# RedundantReg.net
KiCad netlist of a schematic drawn in Altium Designer
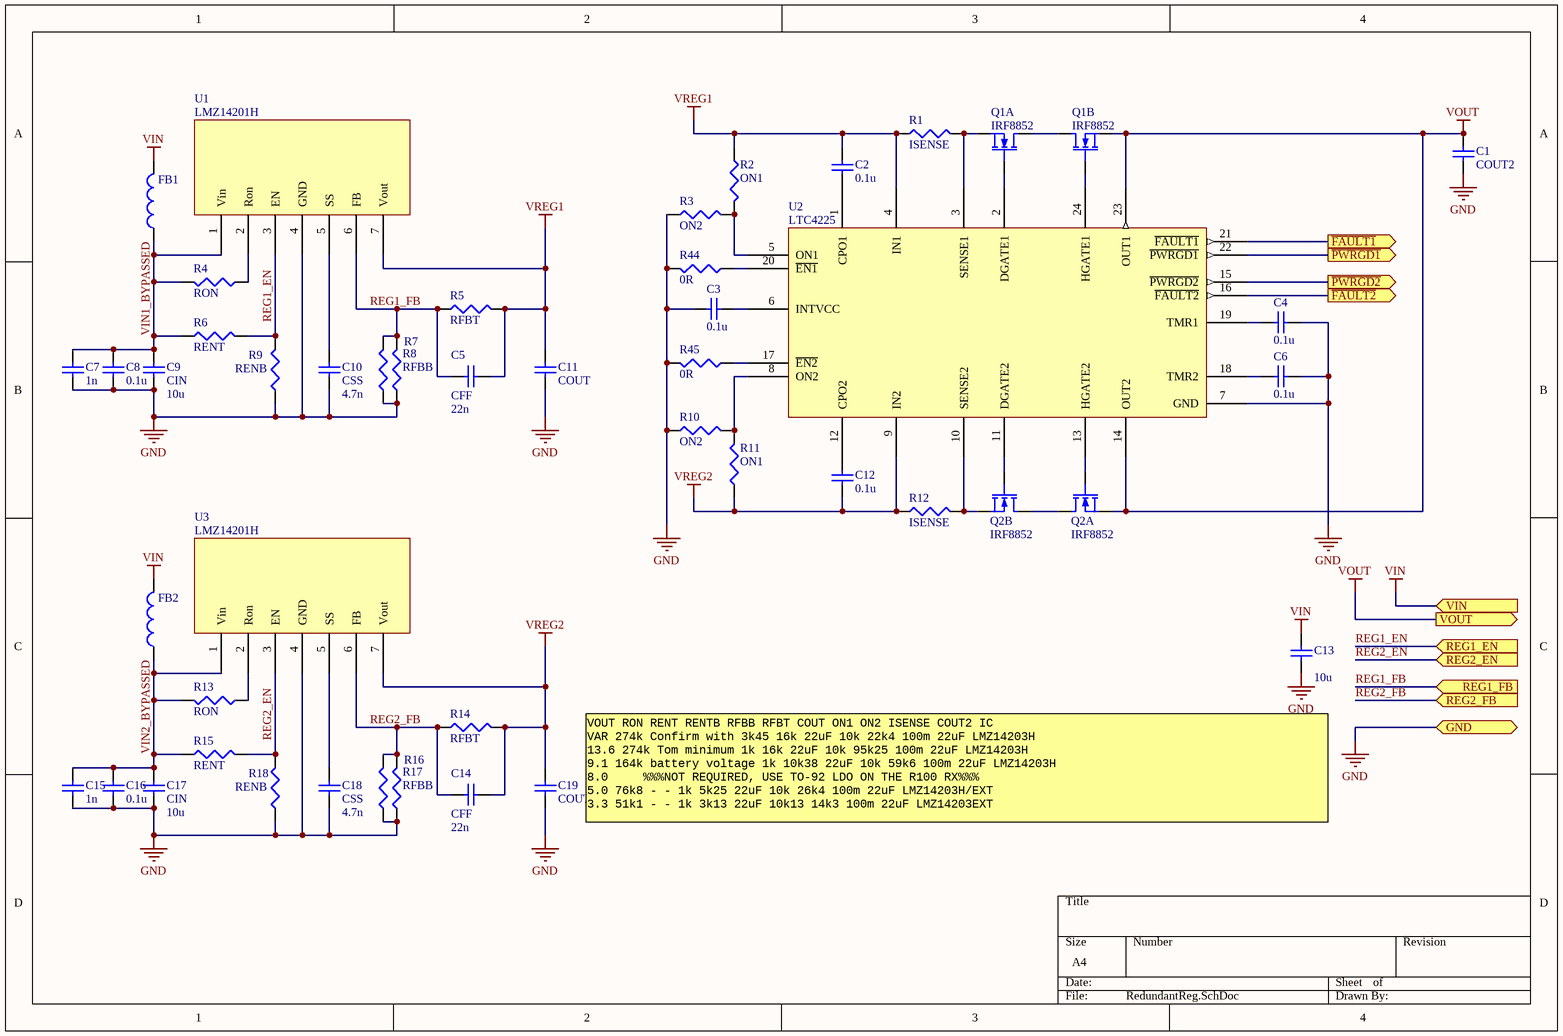
[diagram p0: RedundantReg.SchDoc]

(export (version "E")
  (design (tool "Eeschema 10.0.6"))
  (components
    (comp (ref "C1")
      (value "COUT2")
      (footprint "R1210M")
      (description "Capacitor")
      (fields (field (name "PUBLISHER") "Altium Limited"))
      (libsource (lib "Miscellaneous Devices") (part "Cap"))
    )
    (comp (ref "C2")
      (value "0.1u")
      (footprint "R0805M")
      (description "Capacitor")
      (fields (field (name "PUBLISHER") "Altium Limited"))
      (libsource (lib "Miscellaneous Devices") (part "Cap"))
    )
    (comp (ref "C3")
      (value "0.1u")
      (footprint "R0805M")
      (description "Capacitor")
      (fields (field (name "PUBLISHER") "Altium Limited"))
      (libsource (lib "Miscellaneous Devices") (part "Cap"))
    )
    (comp (ref "C4")
      (value "0.1u")
      (footprint "R0805M")
      (description "Capacitor")
      (fields (field (name "PUBLISHER") "Altium Limited"))
      (libsource (lib "Miscellaneous Devices") (part "Cap"))
    )
    (comp (ref "C5")
      (value "CFF")
      (footprint "R0805M")
      (description "Capacitor")
      (fields (field (name "ALTIUM_VALUE") "22n") (field (name "PUBLISHER") "Altium Limited"))
      (libsource (lib "Miscellaneous Devices") (part "Cap"))
    )
    (comp (ref "C6")
      (value "0.1u")
      (footprint "R0805M")
      (description "Capacitor")
      (fields (field (name "PUBLISHER") "Altium Limited"))
      (libsource (lib "Miscellaneous Devices") (part "Cap"))
    )
    (comp (ref "C7")
      (value "1n")
      (footprint "R0805M")
      (description "Capacitor")
      (fields (field (name "Comment") "CIN") (field (name "PUBLISHER") "Altium Limited"))
      (libsource (lib "Miscellaneous Devices") (part "Cap"))
    )
    (comp (ref "C8")
      (value "0.1u")
      (footprint "R0805M")
      (description "Capacitor")
      (fields (field (name "Comment") "CIN") (field (name "PUBLISHER") "Altium Limited"))
      (libsource (lib "Miscellaneous Devices") (part "Cap"))
    )
    (comp (ref "C9")
      (value "CIN")
      (footprint "R1210M")
      (description "Capacitor")
      (fields (field (name "ALTIUM_VALUE") "10u") (field (name "PUBLISHER") "Altium Limited"))
      (libsource (lib "Miscellaneous Devices") (part "Cap"))
    )
    (comp (ref "C10")
      (value "CSS")
      (footprint "R0805M")
      (description "Capacitor")
      (fields (field (name "ALTIUM_VALUE") "4.7n") (field (name "PUBLISHER") "Altium Limited"))
      (libsource (lib "Miscellaneous Devices") (part "Cap"))
    )
    (comp (ref "C11")
      (value "COUT")
      (footprint "R1210M")
      (description "Capacitor")
      (fields (field (name "PUBLISHER") "Altium Limited"))
      (libsource (lib "Miscellaneous Devices") (part "Cap"))
    )
    (comp (ref "C12")
      (value "0.1u")
      (footprint "R0805M")
      (description "Capacitor")
      (fields (field (name "PUBLISHER") "Altium Limited"))
      (libsource (lib "Miscellaneous Devices") (part "Cap"))
    )
    (comp (ref "C13")
      (value "10u")
      (footprint "R1210M")
      (description "Capacitor")
      (fields (field (name "PUBLISHER") "Altium Limited"))
      (libsource (lib "Miscellaneous Devices") (part "Cap"))
    )
    (comp (ref "C14")
      (value "CFF")
      (footprint "R0805M")
      (description "Capacitor")
      (fields (field (name "ALTIUM_VALUE") "22n") (field (name "PUBLISHER") "Altium Limited"))
      (libsource (lib "Miscellaneous Devices") (part "Cap"))
    )
    (comp (ref "C15")
      (value "1n")
      (footprint "R0805M")
      (description "Capacitor")
      (fields (field (name "Comment") "CIN") (field (name "PUBLISHER") "Altium Limited"))
      (libsource (lib "Miscellaneous Devices") (part "Cap"))
    )
    (comp (ref "C16")
      (value "0.1u")
      (footprint "R0805M")
      (description "Capacitor")
      (fields (field (name "Comment") "CIN") (field (name "PUBLISHER") "Altium Limited"))
      (libsource (lib "Miscellaneous Devices") (part "Cap"))
    )
    (comp (ref "C17")
      (value "CIN")
      (footprint "R1210M")
      (description "Capacitor")
      (fields (field (name "ALTIUM_VALUE") "10u") (field (name "PUBLISHER") "Altium Limited"))
      (libsource (lib "Miscellaneous Devices") (part "Cap"))
    )
    (comp (ref "C18")
      (value "CSS")
      (footprint "R0805M")
      (description "Capacitor")
      (fields (field (name "ALTIUM_VALUE") "4.7n") (field (name "PUBLISHER") "Altium Limited"))
      (libsource (lib "Miscellaneous Devices") (part "Cap"))
    )
    (comp (ref "C19")
      (value "COUT")
      (footprint "R1210M")
      (description "Capacitor")
      (fields (field (name "PUBLISHER") "Altium Limited"))
      (libsource (lib "Miscellaneous Devices") (part "Cap"))
    )
    (comp (ref "FB1")
      (value "~")
      (footprint "R0805M")
      (description "Inductor")
      (fields (field (name "PUBLISHER") "Altium Limited"))
      (libsource (lib "Miscellaneous Devices") (part "Inductor"))
    )
    (comp (ref "FB2")
      (value "~")
      (footprint "R0805M")
      (description "Inductor")
      (fields (field (name "PUBLISHER") "Altium Limited"))
      (libsource (lib "Miscellaneous Devices") (part "Inductor"))
    )
    (comp (ref "Q1")
      (value "IRF8852")
      (footprint "TSSOP8")
      (description "N-Channel MOSFET")
      (fields (field (name "PUBLISHER") "Altium Limited"))
      (libsource (lib "SchLib") (part "IRF8852"))
    )
    (comp (ref "Q2")
      (value "IRF8852")
      (footprint "TSSOP8")
      (description "N-Channel MOSFET")
      (fields (field (name "PUBLISHER") "Altium Limited"))
      (libsource (lib "SchLib") (part "IRF8852"))
    )
    (comp (ref "R1")
      (value "ISENSE")
      (footprint "R0805M")
      (description "Resistor")
      (fields (field (name "PUBLISHER") "Altium Limited"))
      (libsource (lib "Miscellaneous Devices") (part "Res3"))
    )
    (comp (ref "R2")
      (value "ON1")
      (footprint "R0805M")
      (description "Resistor")
      (fields (field (name "PUBLISHER") "Altium Limited"))
      (libsource (lib "Miscellaneous Devices") (part "Res3"))
    )
    (comp (ref "R3")
      (value "ON2")
      (footprint "R0805M")
      (description "Resistor")
      (fields (field (name "PUBLISHER") "Altium Limited"))
      (libsource (lib "Miscellaneous Devices") (part "Res3"))
    )
    (comp (ref "R4")
      (value "RON")
      (footprint "R0805M")
      (description "Resistor")
      (fields (field (name "PUBLISHER") "Altium Limited"))
      (libsource (lib "Miscellaneous Devices") (part "Res3"))
    )
    (comp (ref "R5")
      (value "RFBT")
      (footprint "R0805M")
      (description "Resistor")
      (fields (field (name "PUBLISHER") "Altium Limited"))
      (libsource (lib "Miscellaneous Devices") (part "Res3"))
    )
    (comp (ref "R6")
      (value "RENT")
      (footprint "R0805M")
      (description "Resistor")
      (fields (field (name "PUBLISHER") "Altium Limited"))
      (libsource (lib "Miscellaneous Devices") (part "Res3"))
    )
    (comp (ref "R7")
      (value "RFBB")
      (footprint "R0805M")
      (description "Resistor")
      (fields (field (name "PUBLISHER") "Altium Limited"))
      (libsource (lib "Miscellaneous Devices") (part "Res3"))
    )
    (comp (ref "R8")
      (value "RFBB")
      (footprint "R0805M")
      (description "Resistor")
      (fields (field (name "PUBLISHER") "Altium Limited"))
      (libsource (lib "Miscellaneous Devices") (part "Res3"))
    )
    (comp (ref "R9")
      (value "RENB")
      (footprint "R0805M")
      (description "Resistor")
      (fields (field (name "PUBLISHER") "Altium Limited"))
      (libsource (lib "Miscellaneous Devices") (part "Res3"))
    )
    (comp (ref "R10")
      (value "ON2")
      (footprint "R0805M")
      (description "Resistor")
      (fields (field (name "PUBLISHER") "Altium Limited"))
      (libsource (lib "Miscellaneous Devices") (part "Res3"))
    )
    (comp (ref "R11")
      (value "ON1")
      (footprint "R0805M")
      (description "Resistor")
      (fields (field (name "PUBLISHER") "Altium Limited"))
      (libsource (lib "Miscellaneous Devices") (part "Res3"))
    )
    (comp (ref "R12")
      (value "ISENSE")
      (footprint "R0805M")
      (description "Resistor")
      (fields (field (name "PUBLISHER") "Altium Limited"))
      (libsource (lib "Miscellaneous Devices") (part "Res3"))
    )
    (comp (ref "R13")
      (value "RON")
      (footprint "R0805M")
      (description "Resistor")
      (fields (field (name "PUBLISHER") "Altium Limited"))
      (libsource (lib "Miscellaneous Devices") (part "Res3"))
    )
    (comp (ref "R14")
      (value "RFBT")
      (footprint "R0805M")
      (description "Resistor")
      (fields (field (name "PUBLISHER") "Altium Limited"))
      (libsource (lib "Miscellaneous Devices") (part "Res3"))
    )
    (comp (ref "R15")
      (value "RENT")
      (footprint "R0805M")
      (description "Resistor")
      (fields (field (name "PUBLISHER") "Altium Limited"))
      (libsource (lib "Miscellaneous Devices") (part "Res3"))
    )
    (comp (ref "R16")
      (value "RFBB")
      (footprint "R0805M")
      (description "Resistor")
      (fields (field (name "PUBLISHER") "Altium Limited"))
      (libsource (lib "Miscellaneous Devices") (part "Res3"))
    )
    (comp (ref "R17")
      (value "RFBB")
      (footprint "R0805M")
      (description "Resistor")
      (fields (field (name "PUBLISHER") "Altium Limited"))
      (libsource (lib "Miscellaneous Devices") (part "Res3"))
    )
    (comp (ref "R18")
      (value "RENB")
      (footprint "R0805M")
      (description "Resistor")
      (fields (field (name "PUBLISHER") "Altium Limited"))
      (libsource (lib "Miscellaneous Devices") (part "Res3"))
    )
    (comp (ref "R44")
      (value "0R")
      (footprint "R0805M")
      (description "Resistor")
      (fields (field (name "PUBLISHER") "Altium Limited"))
      (libsource (lib "Miscellaneous Devices") (part "Res3"))
    )
    (comp (ref "R45")
      (value "0R")
      (footprint "R0805M")
      (description "Resistor")
      (fields (field (name "PUBLISHER") "Altium Limited"))
      (libsource (lib "Miscellaneous Devices") (part "Res3"))
    )
    (comp (ref "U1")
      (value "LMZ14201H")
      (footprint "TO-PMOD-7")
      (description "1A SIMPLE SWITCHER® Power Module for High Output  Voltage")
      (libsource (lib "SchLib") (part "LMZ14201H"))
    )
    (comp (ref "U2")
      (value "LTC4225")
      (footprint "SSOP24")
      (description "Dual Ideal Diode and  Hot Swap Controller")
      (libsource (lib "SchLib") (part "LTC4225"))
    )
    (comp (ref "U3")
      (value "LMZ14201H")
      (footprint "TO-PMOD-7")
      (description "1A SIMPLE SWITCHER® Power Module for High Output  Voltage")
      (libsource (lib "SchLib") (part "LMZ14201H"))
    )
  )
  (nets
    (net (code "1") (name "/REG1_EN") (class "Default")
      (node (ref "R6") (pin "2") (pinfunction "2_2") (pintype "passive"))
      (node (ref "R9") (pin "1") (pinfunction "1_1") (pintype "passive"))
      (node (ref "U1") (pin "3") (pinfunction "EN_3") (pintype "passive"))
    )
    (net (code "2") (name "/REG1_FB") (class "Default")
      (node (ref "C5") (pin "1") (pinfunction "1_1") (pintype "passive"))
      (node (ref "R5") (pin "1") (pinfunction "1_1") (pintype "passive"))
      (node (ref "R7") (pin "2") (pinfunction "2_2") (pintype "passive"))
      (node (ref "R8") (pin "2") (pinfunction "2_2") (pintype "passive"))
      (node (ref "U1") (pin "6") (pinfunction "FB_6") (pintype "passive"))
    )
    (net (code "3") (name "/REG2_EN") (class "Default")
      (node (ref "R15") (pin "2") (pinfunction "2_2") (pintype "passive"))
      (node (ref "R18") (pin "1") (pinfunction "1_1") (pintype "passive"))
      (node (ref "U3") (pin "3") (pinfunction "EN_3") (pintype "passive"))
    )
    (net (code "4") (name "/REG2_FB") (class "Default")
      (node (ref "C14") (pin "1") (pinfunction "1_1") (pintype "passive"))
      (node (ref "R14") (pin "1") (pinfunction "1_1") (pintype "passive"))
      (node (ref "R16") (pin "2") (pinfunction "2_2") (pintype "passive"))
      (node (ref "R17") (pin "2") (pinfunction "2_2") (pintype "passive"))
      (node (ref "U3") (pin "6") (pinfunction "FB_6") (pintype "passive"))
    )
    (net (code "5") (name "/VIN1_BYPASSED") (class "Default")
      (node (ref "C7") (pin "2") (pinfunction "2_2") (pintype "passive"))
      (node (ref "C8") (pin "2") (pinfunction "2_2") (pintype "passive"))
      (node (ref "C9") (pin "1") (pinfunction "1_1") (pintype "passive"))
      (node (ref "FB1") (pin "1") (pinfunction "1_1") (pintype "passive"))
      (node (ref "R4") (pin "2") (pinfunction "2_2") (pintype "passive"))
      (node (ref "R6") (pin "1") (pinfunction "1_1") (pintype "passive"))
      (node (ref "U1") (pin "1") (pinfunction "Vin_1") (pintype "passive"))
    )
    (net (code "6") (name "/VIN2_BYPASSED") (class "Default")
      (node (ref "C15") (pin "2") (pinfunction "2_2") (pintype "passive"))
      (node (ref "C16") (pin "2") (pinfunction "2_2") (pintype "passive"))
      (node (ref "C17") (pin "1") (pinfunction "1_1") (pintype "passive"))
      (node (ref "FB2") (pin "1") (pinfunction "1_1") (pintype "passive"))
      (node (ref "R13") (pin "2") (pinfunction "2_2") (pintype "passive"))
      (node (ref "R15") (pin "1") (pinfunction "1_1") (pintype "passive"))
      (node (ref "U3") (pin "1") (pinfunction "Vin_1") (pintype "passive"))
    )
    (net (code "7") (name "/~{FAULT1}") (class "Default")
      (node (ref "U2") (pin "21") (pinfunction "~{FAULT1}_21") (pintype "output"))
    )
    (net (code "8") (name "/~{FAULT2}") (class "Default")
      (node (ref "U2") (pin "16") (pinfunction "~{FAULT2}_16") (pintype "output"))
    )
    (net (code "9") (name "/~{PWRGD1}") (class "Default")
      (node (ref "U2") (pin "22") (pinfunction "~{PWRGD1}_22") (pintype "output"))
    )
    (net (code "10") (name "/~{PWRGD2}") (class "Default")
      (node (ref "U2") (pin "15") (pinfunction "~{PWRGD2}_15") (pintype "output"))
    )
    (net (code "11") (name "GND") (class "Default")
      (node (ref "C1") (pin "1") (pinfunction "1_1") (pintype "passive"))
      (node (ref "C10") (pin "2") (pinfunction "2_2") (pintype "passive"))
      (node (ref "C11") (pin "1") (pinfunction "1_1") (pintype "passive"))
      (node (ref "C13") (pin "2") (pinfunction "2_2") (pintype "passive"))
      (node (ref "C15") (pin "1") (pinfunction "1_1") (pintype "passive"))
      (node (ref "C16") (pin "1") (pinfunction "1_1") (pintype "passive"))
      (node (ref "C17") (pin "2") (pinfunction "2_2") (pintype "passive"))
      (node (ref "C18") (pin "2") (pinfunction "2_2") (pintype "passive"))
      (node (ref "C19") (pin "1") (pinfunction "1_1") (pintype "passive"))
      (node (ref "C3") (pin "2") (pinfunction "2_2") (pintype "passive"))
      (node (ref "C4") (pin "1") (pinfunction "1_1") (pintype "passive"))
      (node (ref "C6") (pin "1") (pinfunction "1_1") (pintype "passive"))
      (node (ref "C7") (pin "1") (pinfunction "1_1") (pintype "passive"))
      (node (ref "C8") (pin "1") (pinfunction "1_1") (pintype "passive"))
      (node (ref "C9") (pin "2") (pinfunction "2_2") (pintype "passive"))
      (node (ref "R10") (pin "1") (pinfunction "1_1") (pintype "passive"))
      (node (ref "R16") (pin "1") (pinfunction "1_1") (pintype "passive"))
      (node (ref "R17") (pin "1") (pinfunction "1_1") (pintype "passive"))
      (node (ref "R18") (pin "2") (pinfunction "2_2") (pintype "passive"))
      (node (ref "R3") (pin "1") (pinfunction "1_1") (pintype "passive"))
      (node (ref "R44") (pin "2") (pinfunction "2_2") (pintype "passive"))
      (node (ref "R45") (pin "2") (pinfunction "2_2") (pintype "passive"))
      (node (ref "R7") (pin "1") (pinfunction "1_1") (pintype "passive"))
      (node (ref "R8") (pin "1") (pinfunction "1_1") (pintype "passive"))
      (node (ref "R9") (pin "2") (pinfunction "2_2") (pintype "passive"))
      (node (ref "U1") (pin "4") (pinfunction "GND_4") (pintype "passive"))
      (node (ref "U2") (pin "7") (pinfunction "GND_7") (pintype "passive"))
      (node (ref "U3") (pin "4") (pinfunction "GND_4") (pintype "passive"))
    )
    (net (code "12") (name "Net-(Q1A-D)") (class "Default")
      (node (ref "Q1") (pin "D1") (pinfunction "D_D1") (pintype "passive"))
      (node (ref "Q1") (pin "D2") (pinfunction "D_D2") (pintype "passive"))
    )
    (net (code "13") (name "Net-(Q1A-G)") (class "Default")
      (node (ref "Q1") (pin "G1") (pinfunction "G_G1") (pintype "passive"))
      (node (ref "U2") (pin "2") (pinfunction "DGATE1_2") (pintype "passive"))
    )
    (net (code "14") (name "Net-(Q1A-S)") (class "Default")
      (node (ref "Q1") (pin "S1") (pinfunction "S_S1") (pintype "passive"))
      (node (ref "R1") (pin "2") (pinfunction "2_2") (pintype "passive"))
      (node (ref "U2") (pin "3") (pinfunction "SENSE1_3") (pintype "passive"))
    )
    (net (code "15") (name "Net-(Q1B-G)") (class "Default")
      (node (ref "Q1") (pin "G2") (pinfunction "G_G2") (pintype "passive"))
      (node (ref "U2") (pin "24") (pinfunction "HGATE1_24") (pintype "passive"))
    )
    (net (code "16") (name "Net-(Q2A-D)") (class "Default")
      (node (ref "Q2") (pin "D1") (pinfunction "D_D1") (pintype "passive"))
      (node (ref "Q2") (pin "D2") (pinfunction "D_D2") (pintype "passive"))
    )
    (net (code "17") (name "Net-(Q2A-G)") (class "Default")
      (node (ref "Q2") (pin "G1") (pinfunction "G_G1") (pintype "passive"))
      (node (ref "U2") (pin "13") (pinfunction "HGATE2_13") (pintype "passive"))
    )
    (net (code "18") (name "Net-(Q2B-G)") (class "Default")
      (node (ref "Q2") (pin "G2") (pinfunction "G_G2") (pintype "passive"))
      (node (ref "U2") (pin "11") (pinfunction "DGATE2_11") (pintype "passive"))
    )
    (net (code "19") (name "Net-(Q2B-S)") (class "Default")
      (node (ref "Q2") (pin "S2") (pinfunction "S_S2") (pintype "passive"))
      (node (ref "R12") (pin "2") (pinfunction "2_2") (pintype "passive"))
      (node (ref "U2") (pin "10") (pinfunction "SENSE2_10") (pintype "passive"))
    )
    (net (code "20") (name "Net-(U1-Ron)") (class "Default")
      (node (ref "R4") (pin "1") (pinfunction "1_1") (pintype "passive"))
      (node (ref "U1") (pin "2") (pinfunction "Ron_2") (pintype "passive"))
    )
    (net (code "21") (name "Net-(U1-SS)") (class "Default")
      (node (ref "C10") (pin "1") (pinfunction "1_1") (pintype "passive"))
      (node (ref "U1") (pin "5") (pinfunction "SS_5") (pintype "passive"))
    )
    (net (code "22") (name "Net-(U2-CPO1)") (class "Default")
      (node (ref "C2") (pin "2") (pinfunction "2_2") (pintype "passive"))
      (node (ref "U2") (pin "1") (pinfunction "CPO1_1") (pintype "passive"))
    )
    (net (code "23") (name "Net-(U2-CPO2)") (class "Default")
      (node (ref "C12") (pin "1") (pinfunction "1_1") (pintype "passive"))
      (node (ref "U2") (pin "12") (pinfunction "CPO2_12") (pintype "passive"))
    )
    (net (code "24") (name "Net-(U2-INTVCC)") (class "Default")
      (node (ref "C3") (pin "1") (pinfunction "1_1") (pintype "passive"))
      (node (ref "U2") (pin "6") (pinfunction "INTVCC_6") (pintype "passive"))
    )
    (net (code "25") (name "Net-(U2-ON1)") (class "Default")
      (node (ref "R2") (pin "2") (pinfunction "2_2") (pintype "passive"))
      (node (ref "R3") (pin "2") (pinfunction "2_2") (pintype "passive"))
      (node (ref "U2") (pin "5") (pinfunction "ON1_5") (pintype "passive"))
    )
    (net (code "26") (name "Net-(U2-ON2)") (class "Default")
      (node (ref "R10") (pin "2") (pinfunction "2_2") (pintype "passive"))
      (node (ref "R11") (pin "2") (pinfunction "2_2") (pintype "passive"))
      (node (ref "U2") (pin "8") (pinfunction "ON2_8") (pintype "passive"))
    )
    (net (code "27") (name "Net-(U2-TMR1)") (class "Default")
      (node (ref "C4") (pin "2") (pinfunction "2_2") (pintype "passive"))
      (node (ref "U2") (pin "19") (pinfunction "TMR1_19") (pintype "passive"))
    )
    (net (code "28") (name "Net-(U2-TMR2)") (class "Default")
      (node (ref "C6") (pin "2") (pinfunction "2_2") (pintype "passive"))
      (node (ref "U2") (pin "18") (pinfunction "TMR2_18") (pintype "passive"))
    )
    (net (code "29") (name "Net-(U2-~{EN1})") (class "Default")
      (node (ref "R44") (pin "1") (pinfunction "1_1") (pintype "passive"))
      (node (ref "U2") (pin "20") (pinfunction "~{EN1}_20") (pintype "passive"))
    )
    (net (code "30") (name "Net-(U2-~{EN2})") (class "Default")
      (node (ref "R45") (pin "1") (pinfunction "1_1") (pintype "passive"))
      (node (ref "U2") (pin "17") (pinfunction "~{EN2}_17") (pintype "passive"))
    )
    (net (code "31") (name "Net-(U3-Ron)") (class "Default")
      (node (ref "R13") (pin "1") (pinfunction "1_1") (pintype "passive"))
      (node (ref "U3") (pin "2") (pinfunction "Ron_2") (pintype "passive"))
    )
    (net (code "32") (name "Net-(U3-SS)") (class "Default")
      (node (ref "C18") (pin "1") (pinfunction "1_1") (pintype "passive"))
      (node (ref "U3") (pin "5") (pinfunction "SS_5") (pintype "passive"))
    )
    (net (code "33") (name "VIN") (class "Default")
      (node (ref "C13") (pin "1") (pinfunction "1_1") (pintype "passive"))
      (node (ref "FB1") (pin "2") (pinfunction "2_2") (pintype "passive"))
      (node (ref "FB2") (pin "2") (pinfunction "2_2") (pintype "passive"))
    )
    (net (code "34") (name "VOUT") (class "Default")
      (node (ref "C1") (pin "2") (pinfunction "2_2") (pintype "passive"))
      (node (ref "Q1") (pin "S2") (pinfunction "S_S2") (pintype "passive"))
      (node (ref "Q2") (pin "S1") (pinfunction "S_S1") (pintype "passive"))
      (node (ref "U2") (pin "14") (pinfunction "OUT2_14") (pintype "passive"))
      (node (ref "U2") (pin "23") (pinfunction "OUT1_23") (pintype "output"))
    )
    (net (code "35") (name "VREG1") (class "Default")
      (node (ref "C11") (pin "2") (pinfunction "2_2") (pintype "passive"))
      (node (ref "C2") (pin "1") (pinfunction "1_1") (pintype "passive"))
      (node (ref "C5") (pin "2") (pinfunction "2_2") (pintype "passive"))
      (node (ref "R1") (pin "1") (pinfunction "1_1") (pintype "passive"))
      (node (ref "R2") (pin "1") (pinfunction "1_1") (pintype "passive"))
      (node (ref "R5") (pin "2") (pinfunction "2_2") (pintype "passive"))
      (node (ref "U1") (pin "7") (pinfunction "Vout_7") (pintype "passive"))
      (node (ref "U2") (pin "4") (pinfunction "IN1_4") (pintype "passive"))
    )
    (net (code "36") (name "VREG2") (class "Default")
      (node (ref "C12") (pin "2") (pinfunction "2_2") (pintype "passive"))
      (node (ref "C14") (pin "2") (pinfunction "2_2") (pintype "passive"))
      (node (ref "C19") (pin "2") (pinfunction "2_2") (pintype "passive"))
      (node (ref "R11") (pin "1") (pinfunction "1_1") (pintype "passive"))
      (node (ref "R12") (pin "1") (pinfunction "1_1") (pintype "passive"))
      (node (ref "R14") (pin "2") (pinfunction "2_2") (pintype "passive"))
      (node (ref "U2") (pin "9") (pinfunction "IN2_9") (pintype "passive"))
      (node (ref "U3") (pin "7") (pinfunction "Vout_7") (pintype "passive"))
    )
  )
)
